# Session_4.net
KiCad netlist of a schematic drawn in EAGLE
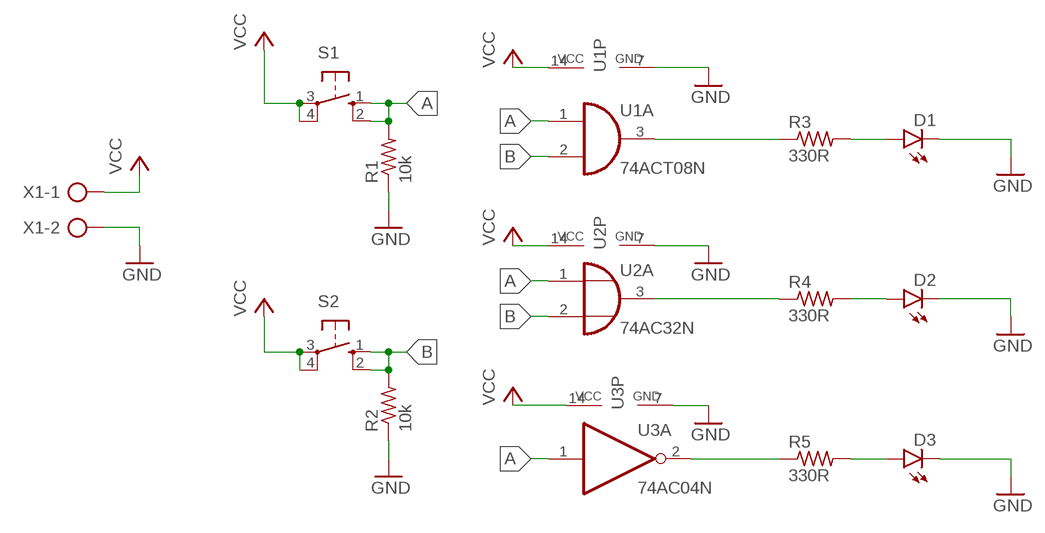
[diagram p0: schematic, sheet 1]

(export (version "E")
  (design (tool "Eeschema 10.0.6"))
  (components
    (comp (ref "D1")
      (value "LED5MM")
      (footprint "eagle-import:LED5MM")
      (libsource (lib "eagle-import") (part "LED5MM"))
    )
    (comp (ref "D2")
      (value "LED5MM")
      (footprint "eagle-import:LED5MM")
      (libsource (lib "eagle-import") (part "LED5MM"))
    )
    (comp (ref "D3")
      (value "LED5MM")
      (footprint "eagle-import:LED5MM")
      (libsource (lib "eagle-import") (part "LED5MM"))
    )
    (comp (ref "R1")
      (value "10k")
      (footprint "eagle-import:0204_7")
      (libsource (lib "eagle-import") (part "R-US_0204/7"))
    )
    (comp (ref "R2")
      (value "10k")
      (footprint "eagle-import:0204_7")
      (libsource (lib "eagle-import") (part "R-US_0204/7"))
    )
    (comp (ref "R3")
      (value "330R")
      (footprint "eagle-import:0204_7")
      (libsource (lib "eagle-import") (part "R-US_0204/7"))
    )
    (comp (ref "R4")
      (value "330R")
      (footprint "eagle-import:0204_7")
      (libsource (lib "eagle-import") (part "R-US_0204/7"))
    )
    (comp (ref "R5")
      (value "330R")
      (footprint "eagle-import:0204_7")
      (libsource (lib "eagle-import") (part "R-US_0204/7"))
    )
    (comp (ref "S1")
      (value "10-XX")
      (footprint "eagle-import:B3F-10XX")
      (fields (field (name "MPN") "B3F-1000"))
      (libsource (lib "eagle-import") (part "10-XX"))
    )
    (comp (ref "S2")
      (value "10-XX")
      (footprint "eagle-import:B3F-10XX")
      (fields (field (name "MPN") "B3F-1000"))
      (libsource (lib "eagle-import") (part "10-XX"))
    )
    (comp (ref "U1")
      (value "74ACT08N")
      (footprint "eagle-import:DIL14")
      (libsource (lib "eagle-import") (part "7408NACT"))
    )
    (comp (ref "U2")
      (value "74AC32N")
      (footprint "eagle-import:DIL14")
      (libsource (lib "eagle-import") (part "7432NAC"))
    )
    (comp (ref "U3")
      (value "74AC04N")
      (footprint "eagle-import:DIL14")
      (libsource (lib "eagle-import") (part "7404NAC"))
    )
    (comp (ref "X1")
      (value "AK500/2")
      (footprint "eagle-import:AK500_2")
      (libsource (lib "eagle-import") (part "AK500/2"))
    )
  )
  (nets
    (net (code "1") (name "A") (class "Default")
      (node (ref "R1") (pin "2") (pinfunction "2_2") (pintype "passive"))
      (node (ref "S1") (pin "1") (pinfunction "S_1") (pintype "passive"))
      (node (ref "S1") (pin "2") (pinfunction "S1_2") (pintype "passive"))
      (node (ref "U1") (pin "1") (pinfunction "I0_1") (pintype "input"))
      (node (ref "U2") (pin "1") (pinfunction "I0_1") (pintype "input"))
      (node (ref "U3") (pin "1") (pinfunction "I_1") (pintype "input"))
    )
    (net (code "2") (name "B") (class "Default")
      (node (ref "R2") (pin "2") (pinfunction "2_2") (pintype "passive"))
      (node (ref "S2") (pin "1") (pinfunction "S_1") (pintype "passive"))
      (node (ref "S2") (pin "2") (pinfunction "S1_2") (pintype "passive"))
      (node (ref "U1") (pin "2") (pinfunction "I1_2") (pintype "input"))
      (node (ref "U2") (pin "2") (pinfunction "I1_2") (pintype "input"))
    )
    (net (code "3") (name "GND") (class "Default")
      (node (ref "D1") (pin "K") (pinfunction "C_K") (pintype "passive"))
      (node (ref "D2") (pin "K") (pinfunction "C_K") (pintype "passive"))
      (node (ref "D3") (pin "K") (pinfunction "C_K") (pintype "passive"))
      (node (ref "R1") (pin "1") (pinfunction "1_1") (pintype "passive"))
      (node (ref "R2") (pin "1") (pinfunction "1_1") (pintype "passive"))
      (node (ref "U1") (pin "7") (pinfunction "GND_7") (pintype "power_in"))
      (node (ref "U2") (pin "7") (pinfunction "GND_7") (pintype "power_in"))
      (node (ref "U3") (pin "7") (pinfunction "GND_7") (pintype "power_in"))
      (node (ref "X1") (pin "2") (pinfunction "KL_2") (pintype "passive"))
    )
    (net (code "4") (name "Net-(D1-PadA)") (class "Default")
      (node (ref "D1") (pin "A") (pinfunction "A_A") (pintype "passive"))
      (node (ref "R3") (pin "2") (pinfunction "2_2") (pintype "passive"))
    )
    (net (code "5") (name "Net-(D2-PadA)") (class "Default")
      (node (ref "D2") (pin "A") (pinfunction "A_A") (pintype "passive"))
      (node (ref "R4") (pin "2") (pinfunction "2_2") (pintype "passive"))
    )
    (net (code "6") (name "Net-(D3-PadA)") (class "Default")
      (node (ref "D3") (pin "A") (pinfunction "A_A") (pintype "passive"))
      (node (ref "R5") (pin "2") (pinfunction "2_2") (pintype "passive"))
    )
    (net (code "7") (name "Net-(U1A-O)") (class "Default")
      (node (ref "R3") (pin "1") (pinfunction "1_1") (pintype "passive"))
      (node (ref "U1") (pin "3") (pinfunction "O_3") (pintype "output"))
    )
    (net (code "8") (name "Net-(U2A-O)") (class "Default")
      (node (ref "R4") (pin "1") (pinfunction "1_1") (pintype "passive"))
      (node (ref "U2") (pin "3") (pinfunction "O_3") (pintype "output"))
    )
    (net (code "9") (name "Net-(U3A-O)") (class "Default")
      (node (ref "R5") (pin "1") (pinfunction "1_1") (pintype "passive"))
      (node (ref "U3") (pin "2") (pinfunction "O_2") (pintype "output"))
    )
    (net (code "10") (name "VCC") (class "Default")
      (node (ref "S1") (pin "3") (pinfunction "P_3") (pintype "passive"))
      (node (ref "S1") (pin "4") (pinfunction "P1_4") (pintype "passive"))
      (node (ref "S2") (pin "3") (pinfunction "P_3") (pintype "passive"))
      (node (ref "S2") (pin "4") (pinfunction "P1_4") (pintype "passive"))
      (node (ref "U1") (pin "14") (pinfunction "VCC_14") (pintype "power_in"))
      (node (ref "U2") (pin "14") (pinfunction "VCC_14") (pintype "power_in"))
      (node (ref "U3") (pin "14") (pinfunction "VCC_14") (pintype "power_in"))
      (node (ref "X1") (pin "1") (pinfunction "KL_1") (pintype "passive"))
    )
  )
)
